# PowerMeter.net
KiCad netlist of a schematic drawn in EAGLE
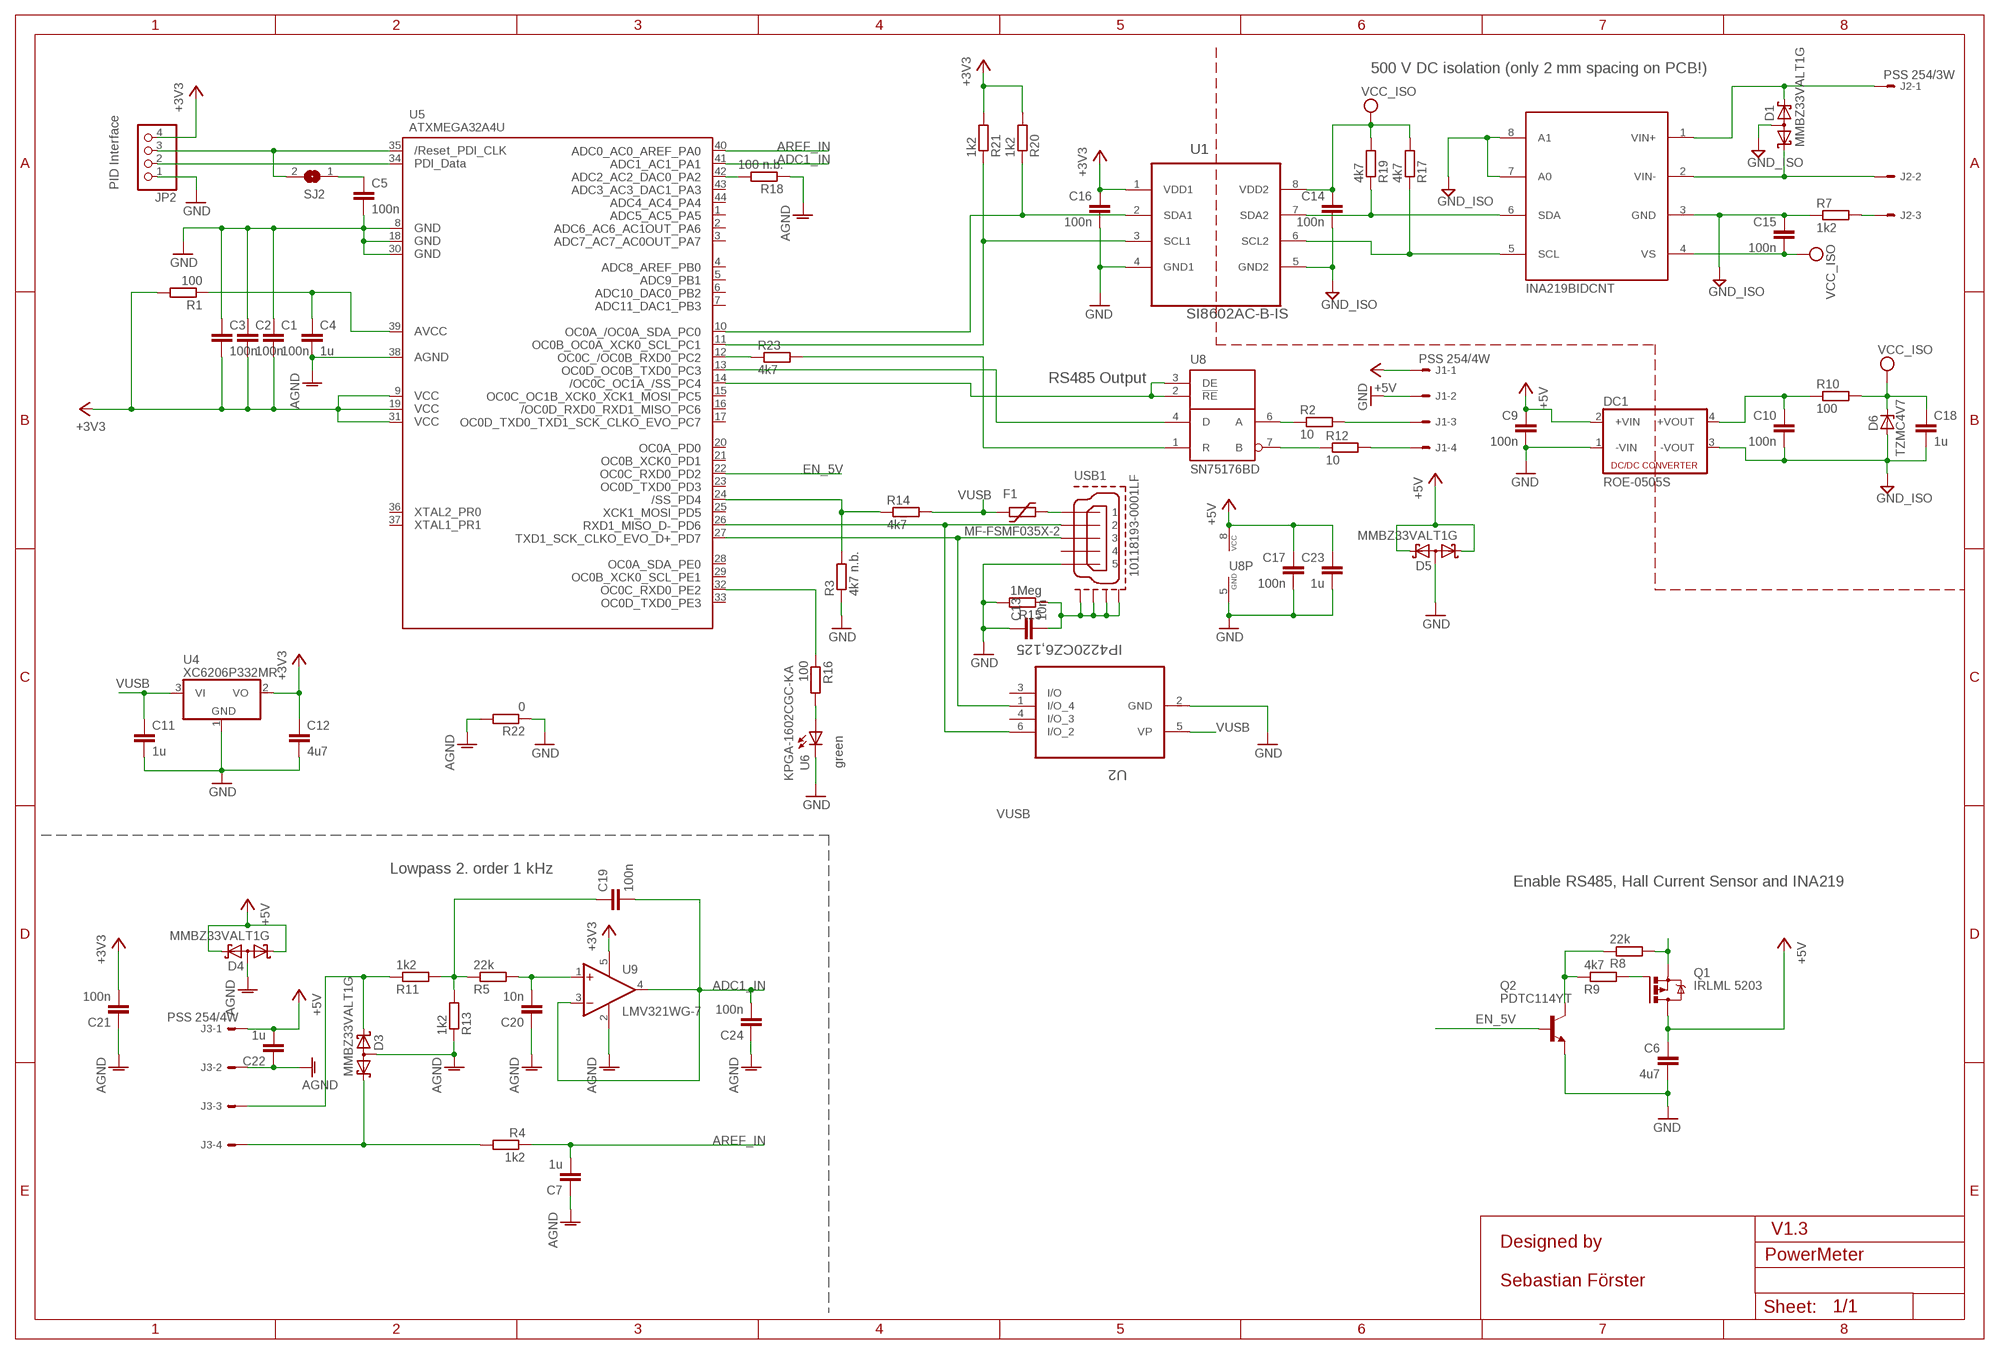
[diagram p0: schematic, sheet 1]

(export (version "E")
  (design (tool "Eeschema 10.0.6"))
  (components
    (comp (ref "C1")
      (value "100n")
      (footprint "eagle-import:C0603")
      (libsource (lib "eagle-import") (part "C-EUC0603"))
    )
    (comp (ref "C2")
      (value "100n")
      (footprint "eagle-import:C0603")
      (libsource (lib "eagle-import") (part "C-EUC0603"))
    )
    (comp (ref "C3")
      (value "100n")
      (footprint "eagle-import:C0603")
      (libsource (lib "eagle-import") (part "C-EUC0603"))
    )
    (comp (ref "C4")
      (value "1u")
      (footprint "eagle-import:C0603")
      (libsource (lib "eagle-import") (part "C-EUC0603"))
    )
    (comp (ref "C5")
      (value "100n")
      (footprint "eagle-import:C0603")
      (libsource (lib "eagle-import") (part "C-EUC0603"))
    )
    (comp (ref "C6")
      (value "4u7")
      (footprint "eagle-import:C0603")
      (libsource (lib "eagle-import") (part "C-EUC0603"))
    )
    (comp (ref "C7")
      (value "1u")
      (footprint "eagle-import:C0603")
      (libsource (lib "eagle-import") (part "C-EUC0603"))
    )
    (comp (ref "C9")
      (value "100n")
      (footprint "eagle-import:C0603")
      (libsource (lib "eagle-import") (part "C-EUC0603"))
    )
    (comp (ref "C10")
      (value "100n")
      (footprint "eagle-import:C0603")
      (libsource (lib "eagle-import") (part "C-EUC0603"))
    )
    (comp (ref "C11")
      (value "1u")
      (footprint "eagle-import:C0603")
      (libsource (lib "eagle-import") (part "C-EUC0603"))
    )
    (comp (ref "C12")
      (value "4u7")
      (footprint "eagle-import:C0603")
      (libsource (lib "eagle-import") (part "C-EUC0603"))
    )
    (comp (ref "C13")
      (value "10n")
      (footprint "eagle-import:C0603")
      (libsource (lib "eagle-import") (part "C-EUC0603"))
    )
    (comp (ref "C14")
      (value "100n")
      (footprint "eagle-import:C0603")
      (libsource (lib "eagle-import") (part "C-EUC0603"))
    )
    (comp (ref "C15")
      (value "100n")
      (footprint "eagle-import:C0603")
      (libsource (lib "eagle-import") (part "C-EUC0603"))
    )
    (comp (ref "C16")
      (value "100n")
      (footprint "eagle-import:C0603")
      (libsource (lib "eagle-import") (part "C-EUC0603"))
    )
    (comp (ref "C17")
      (value "100n")
      (footprint "eagle-import:C0603")
      (libsource (lib "eagle-import") (part "C-EUC0603"))
    )
    (comp (ref "C18")
      (value "1u")
      (footprint "eagle-import:C0603")
      (libsource (lib "eagle-import") (part "C-EUC0603"))
    )
    (comp (ref "C19")
      (value "100n")
      (footprint "eagle-import:C0603")
      (libsource (lib "eagle-import") (part "C-EUC0603"))
    )
    (comp (ref "C20")
      (value "10n")
      (footprint "eagle-import:C0603")
      (libsource (lib "eagle-import") (part "C-EUC0603"))
    )
    (comp (ref "C21")
      (value "100n")
      (footprint "eagle-import:C0603")
      (libsource (lib "eagle-import") (part "C-EUC0603"))
    )
    (comp (ref "C22")
      (value "1u")
      (footprint "eagle-import:C0603")
      (libsource (lib "eagle-import") (part "C-EUC0603"))
    )
    (comp (ref "C23")
      (value "1u")
      (footprint "eagle-import:C0603")
      (libsource (lib "eagle-import") (part "C-EUC0603"))
    )
    (comp (ref "C24")
      (value "100n")
      (footprint "eagle-import:C0603")
      (libsource (lib "eagle-import") (part "C-EUC0603"))
    )
    (comp (ref "D1")
      (value "MMBZ33VALT1G")
      (footprint "eagle-import:SOT23")
      (libsource (lib "eagle-import") (part "BAS40-06"))
    )
    (comp (ref "D3")
      (value "MMBZ33VALT1G")
      (footprint "eagle-import:SOT23")
      (libsource (lib "eagle-import") (part "BAS40-06"))
    )
    (comp (ref "D4")
      (value "MMBZ33VALT1G")
      (footprint "eagle-import:SOT23")
      (libsource (lib "eagle-import") (part "BAS40-06"))
    )
    (comp (ref "D5")
      (value "MMBZ33VALT1G")
      (footprint "eagle-import:SOT23")
      (libsource (lib "eagle-import") (part "BAS40-06"))
    )
    (comp (ref "D6")
      (value "TZMC4V7")
      (footprint "eagle-import:SOD80C")
      (libsource (lib "eagle-import") (part "ZENER-DIODESOD80C"))
    )
    (comp (ref "DC1")
      (value "ROE-0505S")
      (footprint "eagle-import:NME")
      (libsource (lib "eagle-import") (part "NME"))
    )
    (comp (ref "F1")
      (value "MF-FSMF035X-2")
      (footprint "eagle-import:R0603")
      (libsource (lib "eagle-import") (part "PMS1812"))
    )
    (comp (ref "J1")
      (value "PSS 254/4W")
      (footprint "eagle-import:6410-04")
      (libsource (lib "eagle-import") (part "22-?-0427-2041"))
    )
    (comp (ref "J2")
      (value "PSS 254/3W")
      (footprint "eagle-import:6410-03")
      (libsource (lib "eagle-import") (part "22-?-0327-2031"))
    )
    (comp (ref "J3")
      (value "PSS 254/4W")
      (footprint "eagle-import:6410-04")
      (fields (field (name "OC_FARNELL") "unknown") (field (name "OC_NEWARK") "unknown"))
      (libsource (lib "eagle-import") (part "22-?-0427-2041"))
    )
    (comp (ref "JP2")
      (value "PINHD-1X4_2.00")
      (footprint "eagle-import:1X04M")
      (libsource (lib "eagle-import") (part "PINHD-1X4_2.00"))
    )
    (comp (ref "Q1")
      (value "IRLML 5203")
      (footprint "eagle-import:MICRO3")
      (libsource (lib "eagle-import") (part "IRLML5203"))
    )
    (comp (ref "Q2")
      (value "PDTC114YT")
      (footprint "eagle-import:SOT23")
      (libsource (lib "eagle-import") (part "BC848SMDALT1"))
    )
    (comp (ref "R1")
      (value "100")
      (footprint "eagle-import:R0603")
      (libsource (lib "eagle-import") (part "R-EU_R0603"))
    )
    (comp (ref "R2")
      (value "10")
      (footprint "eagle-import:R0603")
      (libsource (lib "eagle-import") (part "R-EU_R0603"))
    )
    (comp (ref "R3")
      (value "4k7 n.b.")
      (footprint "eagle-import:R0603")
      (libsource (lib "eagle-import") (part "R-EU_R0603"))
    )
    (comp (ref "R4")
      (value "1k2")
      (footprint "eagle-import:R0603")
      (libsource (lib "eagle-import") (part "R-EU_R0603"))
    )
    (comp (ref "R5")
      (value "22k")
      (footprint "eagle-import:R0603")
      (libsource (lib "eagle-import") (part "R-EU_R0603"))
    )
    (comp (ref "R7")
      (value "1k2")
      (footprint "eagle-import:R0603")
      (libsource (lib "eagle-import") (part "R-EU_R0603"))
    )
    (comp (ref "R8")
      (value "22k")
      (footprint "eagle-import:R0603")
      (libsource (lib "eagle-import") (part "R-EU_R0603"))
    )
    (comp (ref "R9")
      (value "4k7")
      (footprint "eagle-import:R0603")
      (libsource (lib "eagle-import") (part "R-EU_R0603"))
    )
    (comp (ref "R10")
      (value "100")
      (footprint "eagle-import:R0603")
      (libsource (lib "eagle-import") (part "R-EU_R0603"))
    )
    (comp (ref "R11")
      (value "1k2")
      (footprint "eagle-import:R0603")
      (libsource (lib "eagle-import") (part "R-EU_R0603"))
    )
    (comp (ref "R12")
      (value "10")
      (footprint "eagle-import:R0603")
      (libsource (lib "eagle-import") (part "R-EU_R0603"))
    )
    (comp (ref "R13")
      (value "1k2")
      (footprint "eagle-import:R0603")
      (libsource (lib "eagle-import") (part "R-EU_R0603"))
    )
    (comp (ref "R14")
      (value "4k7")
      (footprint "eagle-import:R0603")
      (libsource (lib "eagle-import") (part "R-EU_R0603"))
    )
    (comp (ref "R15")
      (value "1Meg")
      (footprint "eagle-import:R0603")
      (libsource (lib "eagle-import") (part "R-EU_R0603"))
    )
    (comp (ref "R16")
      (value "100")
      (footprint "eagle-import:R0603")
      (libsource (lib "eagle-import") (part "R-EU_R0603"))
    )
    (comp (ref "R17")
      (value "4k7")
      (footprint "eagle-import:R0603")
      (libsource (lib "eagle-import") (part "R-EU_R0603"))
    )
    (comp (ref "R18")
      (value "100 n.b.")
      (footprint "eagle-import:R0603")
      (libsource (lib "eagle-import") (part "R-EU_R0603"))
    )
    (comp (ref "R19")
      (value "4k7")
      (footprint "eagle-import:R0603")
      (libsource (lib "eagle-import") (part "R-EU_R0603"))
    )
    (comp (ref "R20")
      (value "1k2")
      (footprint "eagle-import:R0603")
      (libsource (lib "eagle-import") (part "R-EU_R0603"))
    )
    (comp (ref "R21")
      (value "1k2")
      (footprint "eagle-import:R0603")
      (libsource (lib "eagle-import") (part "R-EU_R0603"))
    )
    (comp (ref "R22")
      (value "0")
      (footprint "eagle-import:R0603")
      (libsource (lib "eagle-import") (part "R-EU_R0603"))
    )
    (comp (ref "R23")
      (value "4k7")
      (footprint "eagle-import:R0603")
      (libsource (lib "eagle-import") (part "R-EU_R0603"))
    )
    (comp (ref "SJ2") (value "SJ") (footprint "eagle-import:SJ") (libsource (lib "eagle-import") (part "SJ")))
    (comp (ref "U1")
      (value "SI8602AC-B-IS")
      (footprint "eagle-import:SOIC127P600X175-8N")
      (fields (field (name "MPN") "ADUM1250ARZ"))
      (libsource (lib "eagle-import") (part "ADUM1250ARZ"))
    )
    (comp (ref "U2")
      (value "IP4220CZ6,125")
      (footprint "eagle-import:SOT95P275X110-6N")
      (fields (field (name "MPN") "IP4220CZ6"))
      (libsource (lib "eagle-import") (part "IP4220CZ6"))
    )
    (comp (ref "U4")
      (value "XC6206P332MR")
      (footprint "eagle-import:SOT23")
      (libsource (lib "eagle-import") (part "XC6206P332MR"))
    )
    (comp (ref "U5")
      (value "ATXMEGA32A4U")
      (footprint "eagle-import:TQFP44")
      (libsource (lib "eagle-import") (part "AVR_XMEGA_A4U_"))
    )
    (comp (ref "U6")
      (value "KPGA-1602CGC-KA")
      (footprint "eagle-import:CHIP-LED0603")
      (libsource (lib "eagle-import") (part "APA1606SURCK"))
    )
    (comp (ref "U7")
      (value "INA219BIDCNT")
      (footprint "eagle-import:SOT23-6")
      (libsource (lib "eagle-import") (part "INA219"))
    )
    (comp (ref "U8")
      (value "SN75176BD")
      (footprint "eagle-import:SO-08")
      (fields (field (name "MF") "TEXAS INSTRUMENTS") (field (name "MPN") "SN75ALS176AD"))
      (libsource (lib "eagle-import") (part "75ALS176DA"))
    )
    (comp (ref "U9")
      (value "LMV321WG-7")
      (footprint "eagle-import:SOT23-5")
      (libsource (lib "eagle-import") (part "LMV321?M5"))
    )
    (comp (ref "USB1")
      (value "10118193-0001LF")
      (footprint "eagle-import:MOLEX-47364-0001")
      (libsource (lib "eagle-import") (part "MOLEX-47346-0001"))
    )
  )
  (nets
    (net (code "1") (name "+3V3") (class "Default")
      (node (ref "C1") (pin "2") (pinfunction "2_2") (pintype "passive"))
      (node (ref "C12") (pin "1") (pinfunction "1_1") (pintype "passive"))
      (node (ref "C16") (pin "1") (pinfunction "1_1") (pintype "passive"))
      (node (ref "C2") (pin "2") (pinfunction "2_2") (pintype "passive"))
      (node (ref "C21") (pin "2") (pinfunction "2_2") (pintype "passive"))
      (node (ref "C3") (pin "2") (pinfunction "2_2") (pintype "passive"))
      (node (ref "JP2") (pin "4") (pinfunction "4_4") (pintype "passive"))
      (node (ref "R1") (pin "2") (pinfunction "2_2") (pintype "passive"))
      (node (ref "R20") (pin "2") (pinfunction "2_2") (pintype "passive"))
      (node (ref "R21") (pin "2") (pinfunction "2_2") (pintype "passive"))
      (node (ref "U1") (pin "1") (pinfunction "VDD1_1") (pintype "power_in"))
      (node (ref "U4") (pin "2") (pinfunction "VO_2") (pintype "passive"))
      (node (ref "U5") (pin "19") (pinfunction "VCC2_19") (pintype "bidirectional"))
      (node (ref "U5") (pin "31") (pinfunction "VCC3_31") (pintype "bidirectional"))
      (node (ref "U5") (pin "9") (pinfunction "VCC1_9") (pintype "bidirectional"))
      (node (ref "U9") (pin "5") (pinfunction "V+_5") (pintype "power_in"))
    )
    (net (code "2") (name "+5V") (class "Default")
      (node (ref "C17") (pin "1") (pinfunction "1_1") (pintype "passive"))
      (node (ref "C22") (pin "2") (pinfunction "2_2") (pintype "passive"))
      (node (ref "C23") (pin "1") (pinfunction "1_1") (pintype "passive"))
      (node (ref "C6") (pin "1") (pinfunction "1_1") (pintype "passive"))
      (node (ref "C9") (pin "1") (pinfunction "1_1") (pintype "passive"))
      (node (ref "D4") (pin "1") (pinfunction "K1_1") (pintype "passive"))
      (node (ref "D4") (pin "2") (pinfunction "K2_2") (pintype "passive"))
      (node (ref "D5") (pin "1") (pinfunction "K1_1") (pintype "passive"))
      (node (ref "D5") (pin "2") (pinfunction "K2_2") (pintype "passive"))
      (node (ref "DC1") (pin "2") (pinfunction "+VIN_2") (pintype "passive"))
      (node (ref "J1") (pin "1") (pinfunction "S_1") (pintype "passive"))
      (node (ref "J3") (pin "1") (pinfunction "S_1") (pintype "passive"))
      (node (ref "Q1") (pin "3") (pinfunction "D_3") (pintype "passive"))
      (node (ref "U8") (pin "8") (pinfunction "VCC_8") (pintype "power_in"))
    )
    (net (code "3") (name "ADC1_IN") (class "Default")
      (node (ref "C19") (pin "2") (pinfunction "2_2") (pintype "passive"))
      (node (ref "C24") (pin "2") (pinfunction "2_2") (pintype "passive"))
      (node (ref "U5") (pin "41") (pinfunction "PA1_41") (pintype "bidirectional"))
      (node (ref "U9") (pin "3") (pinfunction "-IN_3") (pintype "input"))
      (node (ref "U9") (pin "4") (pinfunction "OUT_4") (pintype "output"))
    )
    (net (code "4") (name "AGND") (class "Default")
      (node (ref "C20") (pin "1") (pinfunction "1_1") (pintype "passive"))
      (node (ref "C21") (pin "1") (pinfunction "1_1") (pintype "passive"))
      (node (ref "C22") (pin "1") (pinfunction "1_1") (pintype "passive"))
      (node (ref "C24") (pin "1") (pinfunction "1_1") (pintype "passive"))
      (node (ref "C4") (pin "2") (pinfunction "2_2") (pintype "passive"))
      (node (ref "C7") (pin "1") (pinfunction "1_1") (pintype "passive"))
      (node (ref "D3") (pin "3") (pinfunction "AA_3") (pintype "passive"))
      (node (ref "D4") (pin "3") (pinfunction "AA_3") (pintype "passive"))
      (node (ref "J3") (pin "2") (pinfunction "S_2") (pintype "passive"))
      (node (ref "R13") (pin "1") (pinfunction "1_1") (pintype "passive"))
      (node (ref "R18") (pin "1") (pinfunction "1_1") (pintype "passive"))
      (node (ref "R22") (pin "2") (pinfunction "2_2") (pintype "passive"))
      (node (ref "U5") (pin "38") (pinfunction "AGND_38") (pintype "bidirectional"))
      (node (ref "U9") (pin "2") (pinfunction "V-_2") (pintype "power_in"))
    )
    (net (code "5") (name "AREF_IN") (class "Default")
      (node (ref "C7") (pin "2") (pinfunction "2_2") (pintype "passive"))
      (node (ref "R4") (pin "1") (pinfunction "1_1") (pintype "passive"))
      (node (ref "U5") (pin "40") (pinfunction "PA0_40") (pintype "bidirectional"))
    )
    (net (code "6") (name "EN_5V") (class "Default")
      (node (ref "Q2") (pin "1") (pinfunction "B_1") (pintype "passive"))
      (node (ref "U5") (pin "22") (pinfunction "PD2_22") (pintype "bidirectional"))
    )
    (net (code "7") (name "GND") (class "Default")
      (node (ref "C1") (pin "1") (pinfunction "1_1") (pintype "passive"))
      (node (ref "C11") (pin "2") (pinfunction "2_2") (pintype "passive"))
      (node (ref "C12") (pin "2") (pinfunction "2_2") (pintype "passive"))
      (node (ref "C13") (pin "1") (pinfunction "1_1") (pintype "passive"))
      (node (ref "C16") (pin "2") (pinfunction "2_2") (pintype "passive"))
      (node (ref "C17") (pin "2") (pinfunction "2_2") (pintype "passive"))
      (node (ref "C2") (pin "1") (pinfunction "1_1") (pintype "passive"))
      (node (ref "C23") (pin "2") (pinfunction "2_2") (pintype "passive"))
      (node (ref "C3") (pin "1") (pinfunction "1_1") (pintype "passive"))
      (node (ref "C5") (pin "2") (pinfunction "2_2") (pintype "passive"))
      (node (ref "C6") (pin "2") (pinfunction "2_2") (pintype "passive"))
      (node (ref "C9") (pin "2") (pinfunction "2_2") (pintype "passive"))
      (node (ref "D5") (pin "3") (pinfunction "AA_3") (pintype "passive"))
      (node (ref "DC1") (pin "1") (pinfunction "-VIN_1") (pintype "passive"))
      (node (ref "J1") (pin "2") (pinfunction "S_2") (pintype "passive"))
      (node (ref "JP2") (pin "1") (pinfunction "1_1") (pintype "passive"))
      (node (ref "Q2") (pin "2") (pinfunction "E_2") (pintype "passive"))
      (node (ref "R15") (pin "2") (pinfunction "2_2") (pintype "passive"))
      (node (ref "R22") (pin "1") (pinfunction "1_1") (pintype "passive"))
      (node (ref "R3") (pin "1") (pinfunction "1_1") (pintype "passive"))
      (node (ref "U1") (pin "4") (pinfunction "GND1_4") (pintype "passive"))
      (node (ref "U2") (pin "2") (pinfunction "GND_2") (pintype "passive"))
      (node (ref "U4") (pin "1") (pinfunction "GND_1") (pintype "passive"))
      (node (ref "U5") (pin "18") (pinfunction "GND2_18") (pintype "bidirectional"))
      (node (ref "U5") (pin "30") (pinfunction "GND3_30") (pintype "bidirectional"))
      (node (ref "U5") (pin "8") (pinfunction "GND1_8") (pintype "bidirectional"))
      (node (ref "U6") (pin "C") (pinfunction "C_C") (pintype "passive"))
      (node (ref "U8") (pin "5") (pinfunction "GND_5") (pintype "power_in"))
      (node (ref "USB1") (pin "5") (pinfunction "5_5") (pintype "input"))
    )
    (net (code "8") (name "GND1") (class "Default")
      (node (ref "C10") (pin "2") (pinfunction "2_2") (pintype "passive"))
      (node (ref "C14") (pin "2") (pinfunction "2_2") (pintype "passive"))
      (node (ref "C15") (pin "1") (pinfunction "1_1") (pintype "passive"))
      (node (ref "C18") (pin "2") (pinfunction "2_2") (pintype "passive"))
      (node (ref "D1") (pin "3") (pinfunction "AA_3") (pintype "passive"))
      (node (ref "D6") (pin "A") (pinfunction "A_A") (pintype "passive"))
      (node (ref "DC1") (pin "3") (pinfunction "-VOUT_3") (pintype "passive"))
      (node (ref "R7") (pin "1") (pinfunction "1_1") (pintype "passive"))
      (node (ref "U1") (pin "5") (pinfunction "GND2_5") (pintype "passive"))
      (node (ref "U7") (pin "3") (pinfunction "GND_3") (pintype "bidirectional"))
      (node (ref "U7") (pin "7") (pinfunction "A0_7") (pintype "bidirectional"))
      (node (ref "U7") (pin "8") (pinfunction "A1_8") (pintype "bidirectional"))
    )
    (net (code "9") (name "Net-(C5-Pad1)") (class "Default")
      (node (ref "C5") (pin "1") (pinfunction "1_1") (pintype "passive"))
      (node (ref "SJ2") (pin "1") (pinfunction "1_1") (pintype "passive"))
    )
    (net (code "10") (name "Net-(C13-Pad2)") (class "Default")
      (node (ref "C13") (pin "2") (pinfunction "2_2") (pintype "passive"))
      (node (ref "R15") (pin "1") (pinfunction "1_1") (pintype "passive"))
      (node (ref "USB1") (pin "GND1") (pinfunction "GND1_GND1") (pintype "bidirectional"))
      (node (ref "USB1") (pin "GND2") (pinfunction "GND2_GND2") (pintype "bidirectional"))
      (node (ref "USB1") (pin "GND3") (pinfunction "GND3_GND3") (pintype "bidirectional"))
      (node (ref "USB1") (pin "GND4") (pinfunction "GND4_GND4") (pintype "bidirectional"))
    )
    (net (code "11") (name "Net-(C19-Pad1)") (class "Default")
      (node (ref "C19") (pin "1") (pinfunction "1_1") (pintype "passive"))
      (node (ref "R11") (pin "2") (pinfunction "2_2") (pintype "passive"))
      (node (ref "R13") (pin "2") (pinfunction "2_2") (pintype "passive"))
      (node (ref "R5") (pin "1") (pinfunction "1_1") (pintype "passive"))
    )
    (net (code "12") (name "Net-(D1-K1)") (class "Default")
      (node (ref "D1") (pin "1") (pinfunction "K1_1") (pintype "passive"))
      (node (ref "J2") (pin "2") (pinfunction "S_2") (pintype "passive"))
      (node (ref "U7") (pin "2") (pinfunction "VIN-_2") (pintype "bidirectional"))
    )
    (net (code "13") (name "Net-(D1-K2)") (class "Default")
      (node (ref "D1") (pin "2") (pinfunction "K2_2") (pintype "passive"))
      (node (ref "J2") (pin "1") (pinfunction "S_1") (pintype "passive"))
      (node (ref "U7") (pin "1") (pinfunction "VIN+_1") (pintype "bidirectional"))
    )
    (net (code "14") (name "Net-(D3-K1)") (class "Default")
      (node (ref "D3") (pin "1") (pinfunction "K1_1") (pintype "passive"))
      (node (ref "J3") (pin "4") (pinfunction "S_4") (pintype "passive"))
      (node (ref "R4") (pin "2") (pinfunction "2_2") (pintype "passive"))
    )
    (net (code "15") (name "Net-(D3-K2)") (class "Default")
      (node (ref "D3") (pin "2") (pinfunction "K2_2") (pintype "passive"))
      (node (ref "J3") (pin "3") (pinfunction "S_3") (pintype "passive"))
      (node (ref "R11") (pin "1") (pinfunction "1_1") (pintype "passive"))
    )
    (net (code "16") (name "Net-(DC1-+VOUT)") (class "Default")
      (node (ref "C10") (pin "1") (pinfunction "1_1") (pintype "passive"))
      (node (ref "DC1") (pin "4") (pinfunction "+VOUT_4") (pintype "passive"))
      (node (ref "R10") (pin "1") (pinfunction "1_1") (pintype "passive"))
    )
    (net (code "17") (name "Net-(F1-Pad2)") (class "Default")
      (node (ref "F1") (pin "2") (pinfunction "2_2") (pintype "passive"))
      (node (ref "USB1") (pin "1") (pinfunction "1_1") (pintype "input"))
    )
    (net (code "18") (name "Net-(J1C-S)") (class "Default")
      (node (ref "J1") (pin "3") (pinfunction "S_3") (pintype "passive"))
      (node (ref "R2") (pin "2") (pinfunction "2_2") (pintype "passive"))
    )
    (net (code "19") (name "Net-(J1D-S)") (class "Default")
      (node (ref "J1") (pin "4") (pinfunction "S_4") (pintype "passive"))
      (node (ref "R12") (pin "2") (pinfunction "2_2") (pintype "passive"))
    )
    (net (code "20") (name "Net-(J2C-S)") (class "Default")
      (node (ref "J2") (pin "3") (pinfunction "S_3") (pintype "passive"))
      (node (ref "R7") (pin "2") (pinfunction "2_2") (pintype "passive"))
    )
    (net (code "21") (name "Net-(Q1-G)") (class "Default")
      (node (ref "Q1") (pin "1") (pinfunction "G_1") (pintype "passive"))
      (node (ref "R9") (pin "2") (pinfunction "2_2") (pintype "passive"))
    )
    (net (code "22") (name "Net-(Q2-C)") (class "Default")
      (node (ref "Q2") (pin "3") (pinfunction "C_3") (pintype "passive"))
      (node (ref "R8") (pin "1") (pinfunction "1_1") (pintype "passive"))
      (node (ref "R9") (pin "1") (pinfunction "1_1") (pintype "passive"))
    )
    (net (code "23") (name "Net-(R16-Pad2)") (class "Default")
      (node (ref "R16") (pin "2") (pinfunction "2_2") (pintype "passive"))
      (node (ref "U6") (pin "A") (pinfunction "A_A") (pintype "passive"))
    )
    (net (code "24") (name "Net-(U1-SCL1)") (class "Default")
      (node (ref "R21") (pin "1") (pinfunction "1_1") (pintype "passive"))
      (node (ref "U1") (pin "3") (pinfunction "SCL1_3") (pintype "input"))
      (node (ref "U5") (pin "11") (pinfunction "PC1_11") (pintype "bidirectional"))
    )
    (net (code "25") (name "Net-(U1-SCL2)") (class "Default")
      (node (ref "R17") (pin "1") (pinfunction "1_1") (pintype "passive"))
      (node (ref "U1") (pin "6") (pinfunction "SCL2_6") (pintype "input"))
      (node (ref "U7") (pin "5") (pinfunction "SCL_5") (pintype "bidirectional"))
    )
    (net (code "26") (name "Net-(U1-SDA1)") (class "Default")
      (node (ref "R20") (pin "1") (pinfunction "1_1") (pintype "passive"))
      (node (ref "U1") (pin "2") (pinfunction "SDA1_2") (pintype "bidirectional"))
      (node (ref "U5") (pin "10") (pinfunction "PC0_10") (pintype "bidirectional"))
    )
    (net (code "27") (name "Net-(U1-SDA2)") (class "Default")
      (node (ref "R19") (pin "1") (pinfunction "1_1") (pintype "passive"))
      (node (ref "U1") (pin "7") (pinfunction "SDA2_7") (pintype "bidirectional"))
      (node (ref "U7") (pin "6") (pinfunction "SDA_6") (pintype "bidirectional"))
    )
    (net (code "28") (name "Net-(U2-I{slash}O_2)") (class "Default")
      (node (ref "U2") (pin "6") (pinfunction "I/O_2_6") (pintype "bidirectional"))
      (node (ref "U5") (pin "26") (pinfunction "PD6_26") (pintype "bidirectional"))
      (node (ref "USB1") (pin "2") (pinfunction "2_2") (pintype "input"))
    )
    (net (code "29") (name "Net-(U2-I{slash}O_4)") (class "Default")
      (node (ref "U2") (pin "1") (pinfunction "I/O_4_1") (pintype "bidirectional"))
      (node (ref "U5") (pin "27") (pinfunction "PD7_27") (pintype "bidirectional"))
      (node (ref "USB1") (pin "3") (pinfunction "3_3") (pintype "input"))
    )
    (net (code "30") (name "Net-(U5-AVCC)") (class "Default")
      (node (ref "C4") (pin "1") (pinfunction "1_1") (pintype "passive"))
      (node (ref "R1") (pin "1") (pinfunction "1_1") (pintype "passive"))
      (node (ref "U5") (pin "39") (pinfunction "AVCC_39") (pintype "bidirectional"))
    )
    (net (code "31") (name "Net-(U5-PA2)") (class "Default")
      (node (ref "R18") (pin "2") (pinfunction "2_2") (pintype "passive"))
      (node (ref "U5") (pin "42") (pinfunction "PA2_42") (pintype "bidirectional"))
    )
    (net (code "32") (name "Net-(U5-PC2)") (class "Default")
      (node (ref "R23") (pin "1") (pinfunction "1_1") (pintype "passive"))
      (node (ref "U5") (pin "12") (pinfunction "PC2_12") (pintype "bidirectional"))
    )
    (net (code "33") (name "Net-(U5-PC3)") (class "Default")
      (node (ref "U5") (pin "13") (pinfunction "PC3_13") (pintype "bidirectional"))
      (node (ref "U8") (pin "4") (pinfunction "D_4") (pintype "input"))
    )
    (net (code "34") (name "Net-(U5-PC4)") (class "Default")
      (node (ref "U5") (pin "14") (pinfunction "PC4_14") (pintype "bidirectional"))
      (node (ref "U8") (pin "2") (pinfunction "~{RE}_2") (pintype "input"))
      (node (ref "U8") (pin "3") (pinfunction "DE_3") (pintype "input"))
    )
    (net (code "35") (name "Net-(U5-PD4)") (class "Default")
      (node (ref "R14") (pin "1") (pinfunction "1_1") (pintype "passive"))
      (node (ref "R3") (pin "2") (pinfunction "2_2") (pintype "passive"))
      (node (ref "U5") (pin "24") (pinfunction "PD4_24") (pintype "bidirectional"))
    )
    (net (code "36") (name "Net-(U5-PDI_DATA)") (class "Default")
      (node (ref "JP2") (pin "2") (pinfunction "2_2") (pintype "passive"))
      (node (ref "U5") (pin "34") (pinfunction "PDI_DATA_34") (pintype "bidirectional"))
    )
    (net (code "37") (name "Net-(U5-PE2)") (class "Default")
      (node (ref "R16") (pin "1") (pinfunction "1_1") (pintype "passive"))
      (node (ref "U5") (pin "32") (pinfunction "PE2_32") (pintype "bidirectional"))
    )
    (net (code "38") (name "Net-(U5-RESET)") (class "Default")
      (node (ref "JP2") (pin "3") (pinfunction "3_3") (pintype "passive"))
      (node (ref "SJ2") (pin "2") (pinfunction "2_2") (pintype "passive"))
      (node (ref "U5") (pin "35") (pinfunction "RESET_35") (pintype "bidirectional"))
    )
    (net (code "39") (name "Net-(U8A-A)") (class "Default")
      (node (ref "R2") (pin "1") (pinfunction "1_1") (pintype "passive"))
      (node (ref "U8") (pin "6") (pinfunction "A_6") (pintype "bidirectional"))
    )
    (net (code "40") (name "Net-(U8A-B)") (class "Default")
      (node (ref "R12") (pin "1") (pinfunction "1_1") (pintype "passive"))
      (node (ref "U8") (pin "7") (pinfunction "B_7") (pintype "bidirectional"))
    )
    (net (code "41") (name "Net-(U8A-R)") (class "Default")
      (node (ref "R23") (pin "2") (pinfunction "2_2") (pintype "passive"))
      (node (ref "U8") (pin "1") (pinfunction "R_1") (pintype "output"))
    )
    (net (code "42") (name "Net-(U9-+IN)") (class "Default")
      (node (ref "C20") (pin "2") (pinfunction "2_2") (pintype "passive"))
      (node (ref "R5") (pin "2") (pinfunction "2_2") (pintype "passive"))
      (node (ref "U9") (pin "1") (pinfunction "+IN_1") (pintype "input"))
    )
    (net (code "43") (name "VCC") (class "Default")
      (node (ref "C14") (pin "1") (pinfunction "1_1") (pintype "passive"))
      (node (ref "C15") (pin "2") (pinfunction "2_2") (pintype "passive"))
      (node (ref "C18") (pin "1") (pinfunction "1_1") (pintype "passive"))
      (node (ref "D6") (pin "C") (pinfunction "C_C") (pintype "passive"))
      (node (ref "R10") (pin "2") (pinfunction "2_2") (pintype "passive"))
      (node (ref "R17") (pin "2") (pinfunction "2_2") (pintype "passive"))
      (node (ref "R19") (pin "2") (pinfunction "2_2") (pintype "passive"))
      (node (ref "U1") (pin "8") (pinfunction "VDD2_8") (pintype "power_in"))
      (node (ref "U7") (pin "4") (pinfunction "VS_4") (pintype "bidirectional"))
    )
    (net (code "44") (name "VUSB") (class "Default")
      (node (ref "C11") (pin "1") (pinfunction "1_1") (pintype "passive"))
      (node (ref "F1") (pin "1") (pinfunction "1_1") (pintype "passive"))
      (node (ref "Q1") (pin "2") (pinfunction "S_2") (pintype "passive"))
      (node (ref "R14") (pin "2") (pinfunction "2_2") (pintype "passive"))
      (node (ref "R8") (pin "2") (pinfunction "2_2") (pintype "passive"))
      (node (ref "U2") (pin "5") (pinfunction "VP_5") (pintype "power_in"))
      (node (ref "U4") (pin "3") (pinfunction "VI_3") (pintype "input"))
    )
    (net (code "45") (name "unconnected-(U2-I{slash}O-Pad3)") (class "Default")
      (node (ref "U2") (pin "3") (pinfunction "I/O_3") (pintype "bidirectional"))
    )
    (net (code "46") (name "unconnected-(U2-I{slash}O_3-Pad4)") (class "Default")
      (node (ref "U2") (pin "4") (pinfunction "I/O_3_4") (pintype "bidirectional"))
    )
    (net (code "47") (name "unconnected-(U5-PA3-Pad43)") (class "Default")
      (node (ref "U5") (pin "43") (pinfunction "PA3_43") (pintype "bidirectional"))
    )
    (net (code "48") (name "unconnected-(U5-PA4-Pad44)") (class "Default")
      (node (ref "U5") (pin "44") (pinfunction "PA4_44") (pintype "bidirectional"))
    )
    (net (code "49") (name "unconnected-(U5-PA5-Pad1)") (class "Default")
      (node (ref "U5") (pin "1") (pinfunction "PA5_1") (pintype "bidirectional"))
    )
    (net (code "50") (name "unconnected-(U5-PA6-Pad2)") (class "Default")
      (node (ref "U5") (pin "2") (pinfunction "PA6_2") (pintype "bidirectional"))
    )
    (net (code "51") (name "unconnected-(U5-PA7-Pad3)") (class "Default")
      (node (ref "U5") (pin "3") (pinfunction "PA7_3") (pintype "bidirectional"))
    )
    (net (code "52") (name "unconnected-(U5-PB0-Pad4)") (class "Default")
      (node (ref "U5") (pin "4") (pinfunction "PB0_4") (pintype "bidirectional"))
    )
    (net (code "53") (name "unconnected-(U5-PB1-Pad5)") (class "Default")
      (node (ref "U5") (pin "5") (pinfunction "PB1_5") (pintype "bidirectional"))
    )
    (net (code "54") (name "unconnected-(U5-PB2-Pad6)") (class "Default")
      (node (ref "U5") (pin "6") (pinfunction "PB2_6") (pintype "bidirectional"))
    )
    (net (code "55") (name "unconnected-(U5-PB3-Pad7)") (class "Default")
      (node (ref "U5") (pin "7") (pinfunction "PB3_7") (pintype "bidirectional"))
    )
    (net (code "56") (name "unconnected-(U5-PC5-Pad15)") (class "Default")
      (node (ref "U5") (pin "15") (pinfunction "PC5_15") (pintype "bidirectional"))
    )
    (net (code "57") (name "unconnected-(U5-PC6-Pad16)") (class "Default")
      (node (ref "U5") (pin "16") (pinfunction "PC6_16") (pintype "bidirectional"))
    )
    (net (code "58") (name "unconnected-(U5-PC7-Pad17)") (class "Default")
      (node (ref "U5") (pin "17") (pinfunction "PC7_17") (pintype "bidirectional"))
    )
    (net (code "59") (name "unconnected-(U5-PD0-Pad20)") (class "Default")
      (node (ref "U5") (pin "20") (pinfunction "PD0_20") (pintype "bidirectional"))
    )
    (net (code "60") (name "unconnected-(U5-PD1-Pad21)") (class "Default")
      (node (ref "U5") (pin "21") (pinfunction "PD1_21") (pintype "bidirectional"))
    )
    (net (code "61") (name "unconnected-(U5-PD3-Pad23)") (class "Default")
      (node (ref "U5") (pin "23") (pinfunction "PD3_23") (pintype "bidirectional"))
    )
    (net (code "62") (name "unconnected-(U5-PD5-Pad25)") (class "Default")
      (node (ref "U5") (pin "25") (pinfunction "PD5_25") (pintype "bidirectional"))
    )
    (net (code "63") (name "unconnected-(U5-PE0-Pad28)") (class "Default")
      (node (ref "U5") (pin "28") (pinfunction "PE0_28") (pintype "bidirectional"))
    )
    (net (code "64") (name "unconnected-(U5-PE1-Pad29)") (class "Default")
      (node (ref "U5") (pin "29") (pinfunction "PE1_29") (pintype "bidirectional"))
    )
    (net (code "65") (name "unconnected-(U5-PE3-Pad33)") (class "Default")
      (node (ref "U5") (pin "33") (pinfunction "PE3_33") (pintype "bidirectional"))
    )
    (net (code "66") (name "unconnected-(U5-PR0-Pad36)") (class "Default")
      (node (ref "U5") (pin "36") (pinfunction "PR0_36") (pintype "bidirectional"))
    )
    (net (code "67") (name "unconnected-(U5-PR1-Pad37)") (class "Default")
      (node (ref "U5") (pin "37") (pinfunction "PR1_37") (pintype "bidirectional"))
    )
    (net (code "68") (name "unconnected-(USB1-Pad4)") (class "Default")
      (node (ref "USB1") (pin "4") (pinfunction "4_4") (pintype "input"))
    )
  )
)
